# CON_Board_v2.net
KiCad netlist of a schematic drawn in EAGLE
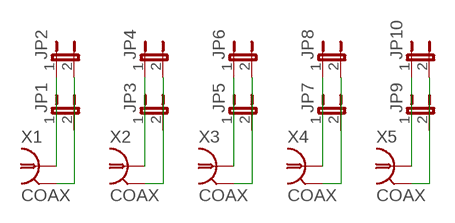
[diagram p0: schematic, sheet 1]

(export (version "E")
  (design (tool "Eeschema 10.0.6"))
  (components
    (comp (ref "JP1")
      (value "JP1E")
      (footprint "eagle-import:JP1")
      (libsource (lib "eagle-import") (part "JP1E"))
    )
    (comp (ref "JP2")
      (value "JP1E")
      (footprint "eagle-import:JP1")
      (libsource (lib "eagle-import") (part "JP1E"))
    )
    (comp (ref "JP3")
      (value "JP1E")
      (footprint "eagle-import:JP1")
      (libsource (lib "eagle-import") (part "JP1E"))
    )
    (comp (ref "JP4")
      (value "JP1E")
      (footprint "eagle-import:JP1")
      (libsource (lib "eagle-import") (part "JP1E"))
    )
    (comp (ref "JP5")
      (value "JP1E")
      (footprint "eagle-import:JP1")
      (libsource (lib "eagle-import") (part "JP1E"))
    )
    (comp (ref "JP6")
      (value "JP1E")
      (footprint "eagle-import:JP1")
      (libsource (lib "eagle-import") (part "JP1E"))
    )
    (comp (ref "JP7")
      (value "JP1E")
      (footprint "eagle-import:JP1")
      (libsource (lib "eagle-import") (part "JP1E"))
    )
    (comp (ref "JP8")
      (value "JP1E")
      (footprint "eagle-import:JP1")
      (libsource (lib "eagle-import") (part "JP1E"))
    )
    (comp (ref "JP9")
      (value "JP1E")
      (footprint "eagle-import:JP1")
      (libsource (lib "eagle-import") (part "JP1E"))
    )
    (comp (ref "JP10")
      (value "JP1E")
      (footprint "eagle-import:JP1")
      (libsource (lib "eagle-import") (part "JP1E"))
    )
    (comp (ref "X1")
      (value "COAX")
      (footprint "eagle-import:31-5329")
      (libsource (lib "eagle-import") (part "31-5329-52RFX31-5329-52RFX"))
    )
    (comp (ref "X2")
      (value "COAX")
      (footprint "eagle-import:31-5329")
      (libsource (lib "eagle-import") (part "31-5329-52RFX31-5329-52RFX"))
    )
    (comp (ref "X3")
      (value "COAX")
      (footprint "eagle-import:31-5329")
      (libsource (lib "eagle-import") (part "31-5329-52RFX31-5329-52RFX"))
    )
    (comp (ref "X4")
      (value "COAX")
      (footprint "eagle-import:31-5329")
      (libsource (lib "eagle-import") (part "31-5329-52RFX31-5329-52RFX"))
    )
    (comp (ref "X5")
      (value "COAX")
      (footprint "eagle-import:31-5329")
      (libsource (lib "eagle-import") (part "31-5329-52RFX31-5329-52RFX"))
    )
  )
  (nets
    (net (code "1") (name "Net-(JP1-Pad1)") (class "Default")
      (node (ref "JP1") (pin "1") (pinfunction "1_1") (pintype "passive"))
      (node (ref "JP2") (pin "1") (pinfunction "1_1") (pintype "passive"))
      (node (ref "X1") (pin "1") (pinfunction "1_1") (pintype "passive"))
    )
    (net (code "2") (name "Net-(JP1-Pad2)") (class "Default")
      (node (ref "JP1") (pin "2") (pinfunction "2_2") (pintype "passive"))
      (node (ref "JP2") (pin "2") (pinfunction "2_2") (pintype "passive"))
      (node (ref "X1") (pin "2") (pinfunction "2_2") (pintype "passive"))
      (node (ref "X1") (pin "3") (pinfunction "2_3") (pintype "passive"))
      (node (ref "X1") (pin "4") (pinfunction "2_4") (pintype "passive"))
      (node (ref "X1") (pin "5") (pinfunction "2_5") (pintype "passive"))
    )
    (net (code "3") (name "Net-(JP3-Pad1)") (class "Default")
      (node (ref "JP3") (pin "1") (pinfunction "1_1") (pintype "passive"))
      (node (ref "JP4") (pin "1") (pinfunction "1_1") (pintype "passive"))
      (node (ref "X2") (pin "1") (pinfunction "1_1") (pintype "passive"))
    )
    (net (code "4") (name "Net-(JP3-Pad2)") (class "Default")
      (node (ref "JP3") (pin "2") (pinfunction "2_2") (pintype "passive"))
      (node (ref "JP4") (pin "2") (pinfunction "2_2") (pintype "passive"))
      (node (ref "X2") (pin "2") (pinfunction "2_2") (pintype "passive"))
      (node (ref "X2") (pin "3") (pinfunction "2_3") (pintype "passive"))
      (node (ref "X2") (pin "4") (pinfunction "2_4") (pintype "passive"))
      (node (ref "X2") (pin "5") (pinfunction "2_5") (pintype "passive"))
    )
    (net (code "5") (name "Net-(JP5-Pad1)") (class "Default")
      (node (ref "JP5") (pin "1") (pinfunction "1_1") (pintype "passive"))
      (node (ref "JP6") (pin "1") (pinfunction "1_1") (pintype "passive"))
      (node (ref "X3") (pin "1") (pinfunction "1_1") (pintype "passive"))
    )
    (net (code "6") (name "Net-(JP5-Pad2)") (class "Default")
      (node (ref "JP5") (pin "2") (pinfunction "2_2") (pintype "passive"))
      (node (ref "JP6") (pin "2") (pinfunction "2_2") (pintype "passive"))
      (node (ref "X3") (pin "2") (pinfunction "2_2") (pintype "passive"))
      (node (ref "X3") (pin "3") (pinfunction "2_3") (pintype "passive"))
      (node (ref "X3") (pin "4") (pinfunction "2_4") (pintype "passive"))
      (node (ref "X3") (pin "5") (pinfunction "2_5") (pintype "passive"))
    )
    (net (code "7") (name "Net-(JP7-Pad1)") (class "Default")
      (node (ref "JP7") (pin "1") (pinfunction "1_1") (pintype "passive"))
      (node (ref "JP8") (pin "1") (pinfunction "1_1") (pintype "passive"))
      (node (ref "X4") (pin "1") (pinfunction "1_1") (pintype "passive"))
    )
    (net (code "8") (name "Net-(JP7-Pad2)") (class "Default")
      (node (ref "JP7") (pin "2") (pinfunction "2_2") (pintype "passive"))
      (node (ref "JP8") (pin "2") (pinfunction "2_2") (pintype "passive"))
      (node (ref "X4") (pin "2") (pinfunction "2_2") (pintype "passive"))
      (node (ref "X4") (pin "3") (pinfunction "2_3") (pintype "passive"))
      (node (ref "X4") (pin "4") (pinfunction "2_4") (pintype "passive"))
      (node (ref "X4") (pin "5") (pinfunction "2_5") (pintype "passive"))
    )
    (net (code "9") (name "Net-(JP10-Pad1)") (class "Default")
      (node (ref "JP10") (pin "1") (pinfunction "1_1") (pintype "passive"))
      (node (ref "JP9") (pin "1") (pinfunction "1_1") (pintype "passive"))
      (node (ref "X5") (pin "1") (pinfunction "1_1") (pintype "passive"))
    )
    (net (code "10") (name "Net-(JP10-Pad2)") (class "Default")
      (node (ref "JP10") (pin "2") (pinfunction "2_2") (pintype "passive"))
      (node (ref "JP9") (pin "2") (pinfunction "2_2") (pintype "passive"))
      (node (ref "X5") (pin "2") (pinfunction "2_2") (pintype "passive"))
      (node (ref "X5") (pin "3") (pinfunction "2_3") (pintype "passive"))
      (node (ref "X5") (pin "4") (pinfunction "2_4") (pintype "passive"))
      (node (ref "X5") (pin "5") (pinfunction "2_5") (pintype "passive"))
    )
  )
)
